# RBP_Dynamixel.net
KiCad netlist of a schematic drawn in EAGLE
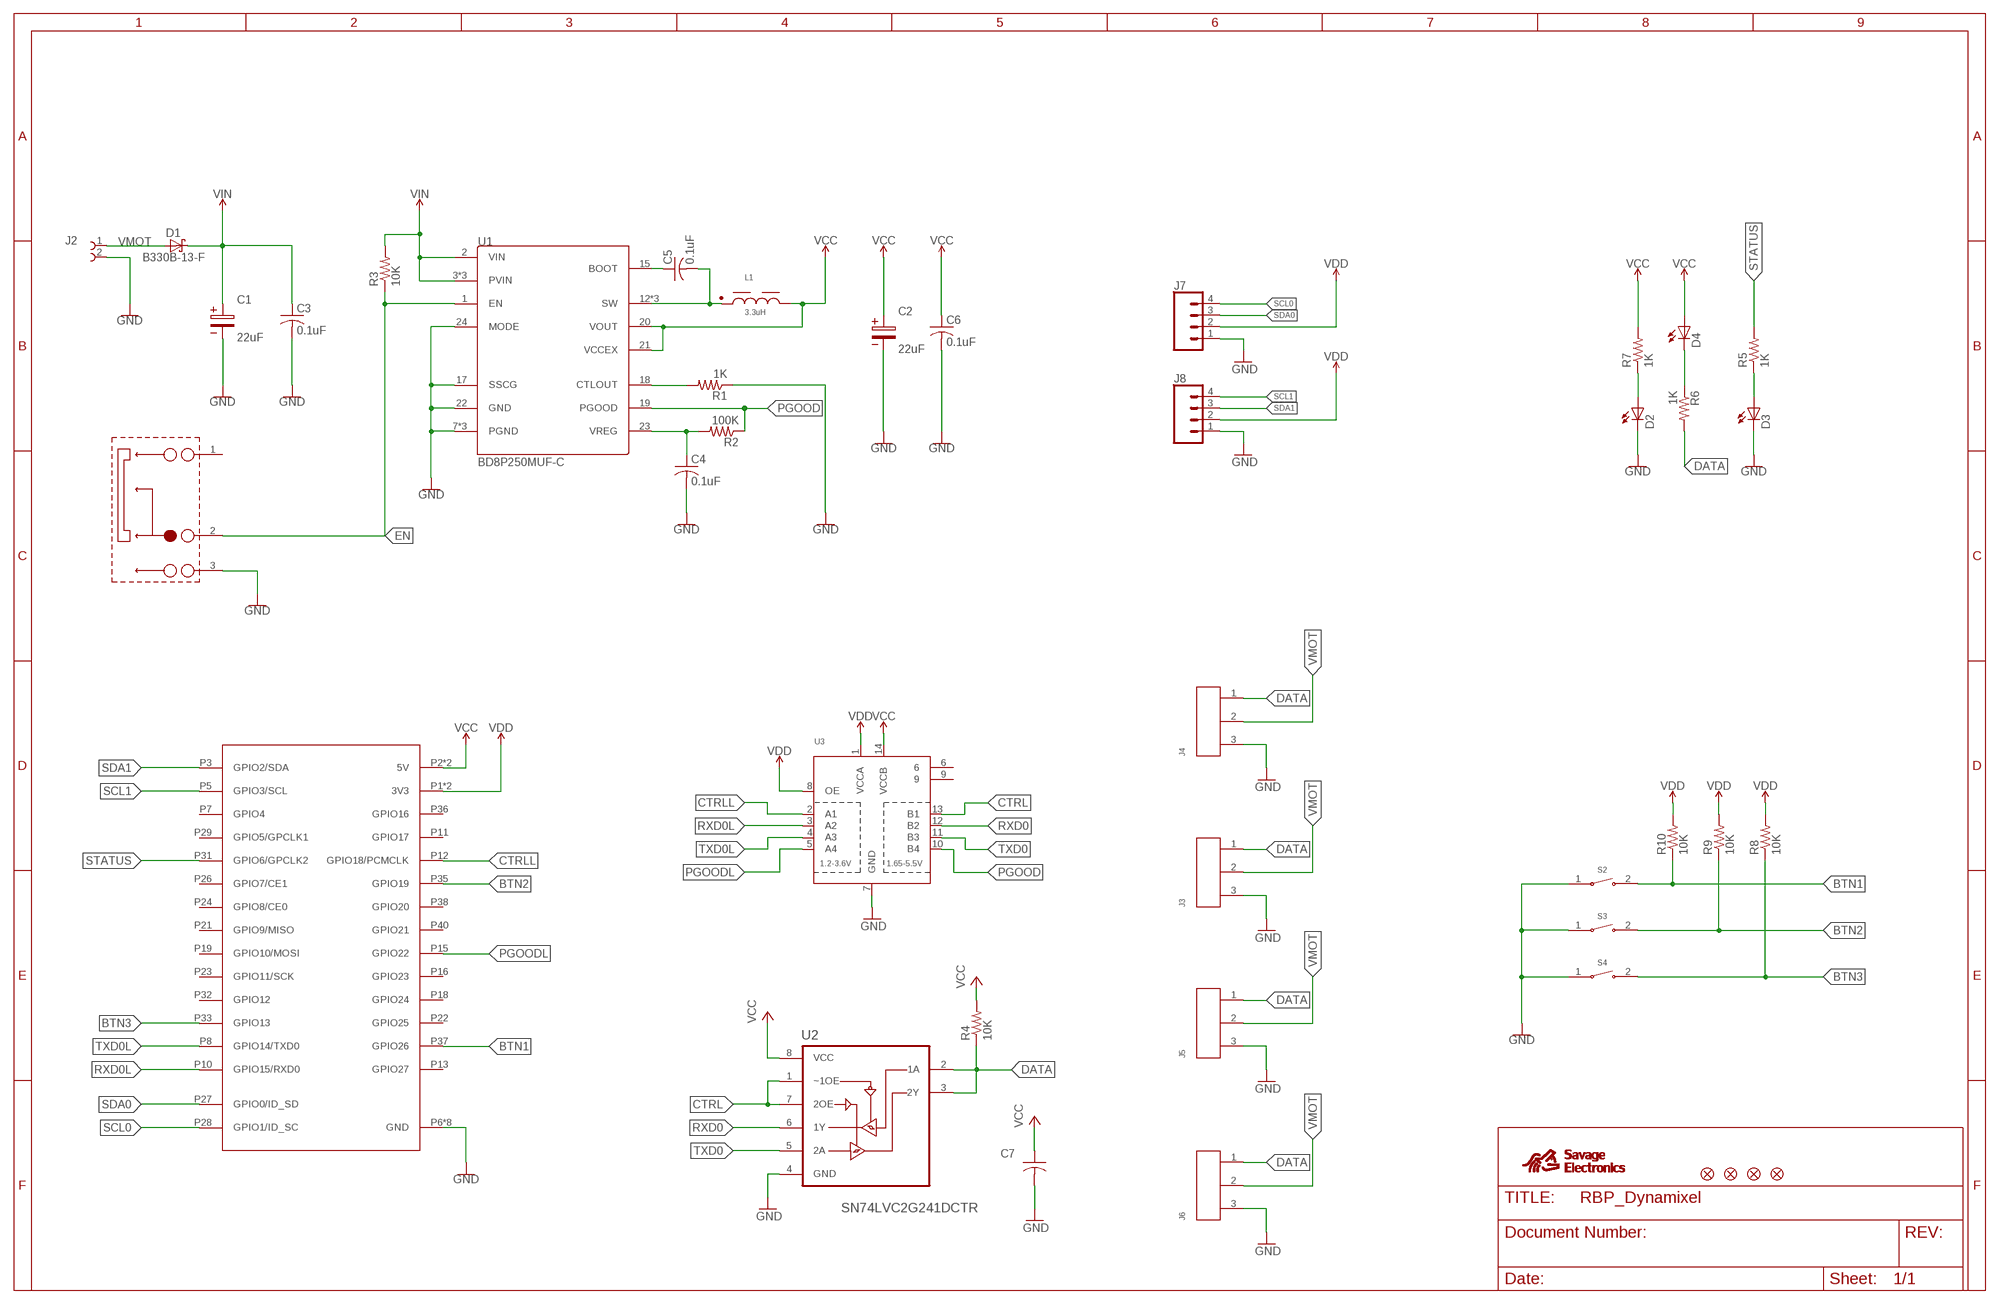
[diagram p0: schematic, sheet 1]

(export (version "E")
  (design (tool "Eeschema 10.0.6"))
  (components
    (comp (ref "C1")
      (value "22uF")
      (footprint "eagle-import:3.5X1.6X2.1(BXCXA)")
      (libsource (lib "eagle-import") (part "WCAP-ASLI_865080643007_6,3X5,5"))
    )
    (comp (ref "C2")
      (value "22uF")
      (footprint "eagle-import:3.5X1.6X2.1(BXCXA)")
      (libsource (lib "eagle-import") (part "WCAP-ASLI_865080643008_6,3X5,5"))
    )
    (comp (ref "C3")
      (value "0.1uF")
      (footprint "eagle-import:C0805")
      (libsource (lib "eagle-import") (part "C-USC0805"))
    )
    (comp (ref "C4")
      (value "0.1uF")
      (footprint "eagle-import:C0805")
      (libsource (lib "eagle-import") (part "C-USC0805"))
    )
    (comp (ref "C5")
      (value "0.1uF")
      (footprint "eagle-import:C0603")
      (libsource (lib "eagle-import") (part "C-USC0603"))
    )
    (comp (ref "C6")
      (value "0.1uF")
      (footprint "eagle-import:C0805")
      (libsource (lib "eagle-import") (part "C-USC0805"))
    )
    (comp (ref "C7")
      (value "1uF")
      (footprint "eagle-import:C0603")
      (libsource (lib "eagle-import") (part "C-USC0603"))
    )
    (comp (ref "D1")
      (value "B330B-13-F")
      (footprint "eagle-import:DIONM4336X250N")
      (libsource (lib "eagle-import") (part "B330B-13-F"))
    )
    (comp (ref "D2")
      (value "LEDCHIP-LED0805")
      (footprint "eagle-import:CHIP-LED0805")
      (libsource (lib "eagle-import") (part "LEDCHIP-LED0805"))
    )
    (comp (ref "D3")
      (value "LEDCHIP-LED0805")
      (footprint "eagle-import:CHIP-LED0805")
      (libsource (lib "eagle-import") (part "LEDCHIP-LED0805"))
    )
    (comp (ref "D4")
      (value "LEDCHIP-LED0805")
      (footprint "eagle-import:CHIP-LED0805")
      (libsource (lib "eagle-import") (part "LEDCHIP-LED0805"))
    )
    (comp (ref "FID1")
      (value "FIDUCIAL\"\"")
      (footprint "eagle-import:FIDUCIAL_1MM")
      (libsource (lib "eagle-import") (part "FIDUCIAL{dblquote}{dblquote}"))
    )
    (comp (ref "FID2")
      (value "FIDUCIAL\"\"")
      (footprint "eagle-import:FIDUCIAL_1MM")
      (libsource (lib "eagle-import") (part "FIDUCIAL{dblquote}{dblquote}"))
    )
    (comp (ref "FID3")
      (value "FIDUCIAL\"\"")
      (footprint "eagle-import:FIDUCIAL_1MM")
      (libsource (lib "eagle-import") (part "FIDUCIAL{dblquote}{dblquote}"))
    )
    (comp (ref "FID4")
      (value "FIDUCIAL\"\"")
      (footprint "eagle-import:FIDUCIAL_1MM")
      (libsource (lib "eagle-import") (part "FIDUCIAL{dblquote}{dblquote}"))
    )
    (comp (ref "J1")
      (value "RBPZERO")
      (footprint "eagle-import:61004021821_RASPBERRYPIZERO")
      (libsource (lib "eagle-import") (part "RBPZERO"))
    )
    (comp (ref "J2")
      (value "691137910002")
      (footprint "eagle-import:691137910002")
      (libsource (lib "eagle-import") (part "691137910002"))
    )
    (comp (ref "J3")
      (value "64600311622")
      (footprint "eagle-import:64600311622")
      (libsource (lib "eagle-import") (part "64600311622"))
    )
    (comp (ref "J4")
      (value "64600311622")
      (footprint "eagle-import:64600311622")
      (libsource (lib "eagle-import") (part "64600311622"))
    )
    (comp (ref "J5")
      (value "64600311622")
      (footprint "eagle-import:64600311622")
      (libsource (lib "eagle-import") (part "64600311622"))
    )
    (comp (ref "J6")
      (value "64600311622")
      (footprint "eagle-import:64600311622")
      (libsource (lib "eagle-import") (part "64600311622"))
    )
    (comp (ref "J7")
      (value "CONN_04SMD2")
      (footprint "eagle-import:1X04_1MM_RA")
      (libsource (lib "eagle-import") (part "CONN_04SMD2"))
    )
    (comp (ref "J8")
      (value "CONN_04SMD2")
      (footprint "eagle-import:1X04_1MM_RA")
      (libsource (lib "eagle-import") (part "CONN_04SMD2"))
    )
    (comp (ref "L1")
      (value "3.3uH")
      (footprint "eagle-import:WE-LQFS_48X8")
      (libsource (lib "eagle-import") (part "WE-LQFS_4818_74406042022"))
    )
    (comp (ref "R1")
      (value "1K")
      (footprint "eagle-import:R0805")
      (libsource (lib "eagle-import") (part "R-US_R0805"))
    )
    (comp (ref "R2")
      (value "100K")
      (footprint "eagle-import:R0805")
      (libsource (lib "eagle-import") (part "R-US_R0805"))
    )
    (comp (ref "R3")
      (value "10K")
      (footprint "eagle-import:R0805")
      (libsource (lib "eagle-import") (part "R-US_R0805"))
    )
    (comp (ref "R4")
      (value "10K")
      (footprint "eagle-import:R0805")
      (libsource (lib "eagle-import") (part "R-US_R0805"))
    )
    (comp (ref "R5")
      (value "1K")
      (footprint "eagle-import:R0805")
      (libsource (lib "eagle-import") (part "R-US_R0805"))
    )
    (comp (ref "R6")
      (value "1K")
      (footprint "eagle-import:R0805")
      (libsource (lib "eagle-import") (part "R-US_R0805"))
    )
    (comp (ref "R7")
      (value "1K")
      (footprint "eagle-import:R0805")
      (libsource (lib "eagle-import") (part "R-US_R0805"))
    )
    (comp (ref "R8")
      (value "10K")
      (footprint "eagle-import:R0805")
      (libsource (lib "eagle-import") (part "R-US_R0805"))
    )
    (comp (ref "R9")
      (value "10K")
      (footprint "eagle-import:R0805")
      (libsource (lib "eagle-import") (part "R-US_R0805"))
    )
    (comp (ref "R10")
      (value "10K")
      (footprint "eagle-import:R0805")
      (libsource (lib "eagle-import") (part "R-US_R0805"))
    )
    (comp (ref "S1")
      (value "450404015514")
      (footprint "eagle-import:450404015514")
      (libsource (lib "eagle-import") (part "450404015514"))
    )
    (comp (ref "S2")
      (value "434123025826-2PIN")
      (footprint "eagle-import:434123025826-2PIN")
      (libsource (lib "eagle-import") (part "434123025826-2PIN"))
    )
    (comp (ref "S3")
      (value "434123025826-2PIN")
      (footprint "eagle-import:434123025826-2PIN")
      (libsource (lib "eagle-import") (part "434123025826-2PIN"))
    )
    (comp (ref "S4")
      (value "434123025826-2PIN")
      (footprint "eagle-import:434123025826-2PIN")
      (libsource (lib "eagle-import") (part "434123025826-2PIN"))
    )
    (comp (ref "U1")
      (value "BD8P250MUF-C")
      (footprint "eagle-import:QFN50P400X400X100-25N")
      (libsource (lib "eagle-import") (part "BD8P250MUF-C"))
    )
    (comp (ref "U2")
      (value "SN74LVC2G241DCTR")
      (footprint "eagle-import:SOP65P400X130-8N")
      (fields (field (name "MF") "Texas Instruments") (field (name "MP") "SN74LVC2G241"))
      (libsource (lib "eagle-import") (part "SN74LVC2G241"))
    )
    (comp (ref "U3")
      (value "TXB0104PWR")
      (footprint "eagle-import:TSSOP14")
      (libsource (lib "eagle-import") (part "TXB0104PWR"))
    )
  )
  (nets
    (net (code "1") (name "BTN1") (class "Default")
      (node (ref "J1") (pin "P37") (pinfunction "GPIO26_P37") (pintype "bidirectional"))
      (node (ref "R10") (pin "1") (pinfunction "1_1") (pintype "passive"))
      (node (ref "S2") (pin "2") (pinfunction "2_2") (pintype "passive"))
    )
    (net (code "2") (name "BTN2") (class "Default")
      (node (ref "J1") (pin "P35") (pinfunction "GPIO19_P35") (pintype "bidirectional"))
      (node (ref "R9") (pin "1") (pinfunction "1_1") (pintype "passive"))
      (node (ref "S3") (pin "2") (pinfunction "2_2") (pintype "passive"))
    )
    (net (code "3") (name "BTN3") (class "Default")
      (node (ref "J1") (pin "P33") (pinfunction "GPIO13_P33") (pintype "bidirectional"))
      (node (ref "R8") (pin "1") (pinfunction "1_1") (pintype "passive"))
      (node (ref "S4") (pin "2") (pinfunction "2_2") (pintype "passive"))
    )
    (net (code "4") (name "CTRL") (class "Default")
      (node (ref "U2") (pin "1") (pinfunction "~{1OE}_1") (pintype "input"))
      (node (ref "U2") (pin "7") (pinfunction "2OE_7") (pintype "input"))
      (node (ref "U3") (pin "13") (pinfunction "B1_13") (pintype "bidirectional"))
    )
    (net (code "5") (name "CTRLL") (class "Default")
      (node (ref "J1") (pin "P12") (pinfunction "GPIO18/PCMCLK_P12") (pintype "bidirectional"))
      (node (ref "U3") (pin "2") (pinfunction "A1_2") (pintype "bidirectional"))
    )
    (net (code "6") (name "DATA") (class "Default")
      (node (ref "J3") (pin "1") (pinfunction "1_1") (pintype "passive"))
      (node (ref "J4") (pin "1") (pinfunction "1_1") (pintype "passive"))
      (node (ref "J5") (pin "1") (pinfunction "1_1") (pintype "passive"))
      (node (ref "J6") (pin "1") (pinfunction "1_1") (pintype "passive"))
      (node (ref "R4") (pin "1") (pinfunction "1_1") (pintype "passive"))
      (node (ref "R6") (pin "2") (pinfunction "2_2") (pintype "passive"))
      (node (ref "U2") (pin "2") (pinfunction "1A_2") (pintype "input"))
      (node (ref "U2") (pin "3") (pinfunction "2Y_3") (pintype "output"))
    )
    (net (code "7") (name "EN") (class "Default")
      (node (ref "R3") (pin "1") (pinfunction "1_1") (pintype "passive"))
      (node (ref "S1") (pin "2") (pinfunction "2_2") (pintype "passive"))
      (node (ref "U1") (pin "1") (pinfunction "EN_1") (pintype "bidirectional"))
    )
    (net (code "8") (name "GND") (class "Default")
      (node (ref "C1") (pin "2") (pinfunction "2_2") (pintype "passive"))
      (node (ref "C2") (pin "2") (pinfunction "2_2") (pintype "passive"))
      (node (ref "C3") (pin "2") (pinfunction "2_2") (pintype "passive"))
      (node (ref "C4") (pin "2") (pinfunction "2_2") (pintype "passive"))
      (node (ref "C6") (pin "2") (pinfunction "2_2") (pintype "passive"))
      (node (ref "C7") (pin "2") (pinfunction "2_2") (pintype "passive"))
      (node (ref "D2") (pin "C") (pinfunction "C_C") (pintype "passive"))
      (node (ref "D3") (pin "C") (pinfunction "C_C") (pintype "passive"))
      (node (ref "J1") (pin "P14") (pinfunction "GND_P14") (pintype "bidirectional"))
      (node (ref "J1") (pin "P20") (pinfunction "GND_P20") (pintype "bidirectional"))
      (node (ref "J1") (pin "P25") (pinfunction "GND_P25") (pintype "bidirectional"))
      (node (ref "J1") (pin "P30") (pinfunction "GND_P30") (pintype "bidirectional"))
      (node (ref "J1") (pin "P34") (pinfunction "GND_P34") (pintype "bidirectional"))
      (node (ref "J1") (pin "P39") (pinfunction "GND_P39") (pintype "bidirectional"))
      (node (ref "J1") (pin "P6") (pinfunction "GND_P6") (pintype "bidirectional"))
      (node (ref "J1") (pin "P9") (pinfunction "GND_P9") (pintype "bidirectional"))
      (node (ref "J2") (pin "2") (pinfunction "2_2") (pintype "passive"))
      (node (ref "J3") (pin "3") (pinfunction "3_3") (pintype "passive"))
      (node (ref "J4") (pin "3") (pinfunction "3_3") (pintype "passive"))
      (node (ref "J5") (pin "3") (pinfunction "3_3") (pintype "passive"))
      (node (ref "J6") (pin "3") (pinfunction "3_3") (pintype "passive"))
      (node (ref "J7") (pin "1") (pinfunction "1_1") (pintype "passive"))
      (node (ref "J8") (pin "1") (pinfunction "1_1") (pintype "passive"))
      (node (ref "R1") (pin "1") (pinfunction "1_1") (pintype "passive"))
      (node (ref "S1") (pin "3") (pinfunction "3_3") (pintype "passive"))
      (node (ref "S2") (pin "1") (pinfunction "1_1") (pintype "passive"))
      (node (ref "S3") (pin "1") (pinfunction "1_1") (pintype "passive"))
      (node (ref "S4") (pin "1") (pinfunction "1_1") (pintype "passive"))
      (node (ref "U1") (pin "17") (pinfunction "SSCG_17") (pintype "bidirectional"))
      (node (ref "U1") (pin "22") (pinfunction "GND_22") (pintype "bidirectional"))
      (node (ref "U1") (pin "24") (pinfunction "MODE_24") (pintype "bidirectional"))
      (node (ref "U1") (pin "25") (pinfunction "PGND_25") (pintype "bidirectional"))
      (node (ref "U1") (pin "7") (pinfunction "PGND_7") (pintype "bidirectional"))
      (node (ref "U1") (pin "8") (pinfunction "PGND_8") (pintype "bidirectional"))
      (node (ref "U2") (pin "4") (pinfunction "GND_4") (pintype "passive"))
      (node (ref "U3") (pin "7") (pinfunction "GND_7") (pintype "bidirectional"))
    )
    (net (code "9") (name "Net-(C5-Pad2)") (class "Default")
      (node (ref "C5") (pin "2") (pinfunction "2_2") (pintype "passive"))
      (node (ref "L1") (pin "1") (pinfunction "1_1") (pintype "passive"))
      (node (ref "U1") (pin "12") (pinfunction "SW_12") (pintype "bidirectional"))
      (node (ref "U1") (pin "13") (pinfunction "SW_13") (pintype "bidirectional"))
      (node (ref "U1") (pin "14") (pinfunction "SW_14") (pintype "bidirectional"))
    )
    (net (code "10") (name "Net-(D2-PadA)") (class "Default")
      (node (ref "D2") (pin "A") (pinfunction "A_A") (pintype "passive"))
      (node (ref "R7") (pin "1") (pinfunction "1_1") (pintype "passive"))
    )
    (net (code "11") (name "Net-(D3-PadA)") (class "Default")
      (node (ref "D3") (pin "A") (pinfunction "A_A") (pintype "passive"))
      (node (ref "R5") (pin "1") (pinfunction "1_1") (pintype "passive"))
    )
    (net (code "12") (name "Net-(D4-PadC)") (class "Default")
      (node (ref "D4") (pin "C") (pinfunction "C_C") (pintype "passive"))
      (node (ref "R6") (pin "1") (pinfunction "1_1") (pintype "passive"))
    )
    (net (code "13") (name "Net-(U1-BOOT)") (class "Default")
      (node (ref "C5") (pin "1") (pinfunction "1_1") (pintype "passive"))
      (node (ref "U1") (pin "15") (pinfunction "BOOT_15") (pintype "bidirectional"))
    )
    (net (code "14") (name "Net-(U1-CTLOUT)") (class "Default")
      (node (ref "R1") (pin "2") (pinfunction "2_2") (pintype "passive"))
      (node (ref "U1") (pin "18") (pinfunction "CTLOUT_18") (pintype "bidirectional"))
    )
    (net (code "15") (name "Net-(U1-VREG)") (class "Default")
      (node (ref "C4") (pin "1") (pinfunction "1_1") (pintype "passive"))
      (node (ref "R2") (pin "2") (pinfunction "2_2") (pintype "passive"))
      (node (ref "U1") (pin "23") (pinfunction "VREG_23") (pintype "bidirectional"))
    )
    (net (code "16") (name "PGOOD") (class "Default")
      (node (ref "R2") (pin "1") (pinfunction "1_1") (pintype "passive"))
      (node (ref "U1") (pin "19") (pinfunction "PGOOD_19") (pintype "bidirectional"))
      (node (ref "U3") (pin "10") (pinfunction "B4_10") (pintype "bidirectional"))
    )
    (net (code "17") (name "PGOODL") (class "Default")
      (node (ref "J1") (pin "P15") (pinfunction "GPIO22_P15") (pintype "bidirectional"))
      (node (ref "U3") (pin "5") (pinfunction "A4_5") (pintype "bidirectional"))
    )
    (net (code "18") (name "RXD0") (class "Default")
      (node (ref "U2") (pin "6") (pinfunction "1Y_6") (pintype "output"))
      (node (ref "U3") (pin "12") (pinfunction "B2_12") (pintype "bidirectional"))
    )
    (net (code "19") (name "RXD0L") (class "Default")
      (node (ref "J1") (pin "P10") (pinfunction "GPIO15/RXD0_P10") (pintype "bidirectional"))
      (node (ref "U3") (pin "3") (pinfunction "A2_3") (pintype "bidirectional"))
    )
    (net (code "20") (name "SCL0") (class "Default")
      (node (ref "J1") (pin "P28") (pinfunction "GPIO1/ID_SC_P28") (pintype "bidirectional"))
      (node (ref "J7") (pin "4") (pinfunction "4_4") (pintype "passive"))
    )
    (net (code "21") (name "SCL1") (class "Default")
      (node (ref "J1") (pin "P5") (pinfunction "GPIO3/SCL_P5") (pintype "bidirectional"))
      (node (ref "J8") (pin "4") (pinfunction "4_4") (pintype "passive"))
    )
    (net (code "22") (name "SDA0") (class "Default")
      (node (ref "J1") (pin "P27") (pinfunction "GPIO0/ID_SD_P27") (pintype "bidirectional"))
      (node (ref "J7") (pin "3") (pinfunction "3_3") (pintype "passive"))
    )
    (net (code "23") (name "SDA1") (class "Default")
      (node (ref "J1") (pin "P3") (pinfunction "GPIO2/SDA_P3") (pintype "bidirectional"))
      (node (ref "J8") (pin "3") (pinfunction "3_3") (pintype "passive"))
    )
    (net (code "24") (name "STATUS") (class "Default")
      (node (ref "J1") (pin "P31") (pinfunction "GPIO6/GPCLK2_P31") (pintype "bidirectional"))
      (node (ref "R5") (pin "2") (pinfunction "2_2") (pintype "passive"))
    )
    (net (code "25") (name "TXD0") (class "Default")
      (node (ref "U2") (pin "5") (pinfunction "2A_5") (pintype "input"))
      (node (ref "U3") (pin "11") (pinfunction "B3_11") (pintype "bidirectional"))
    )
    (net (code "26") (name "TXD0L") (class "Default")
      (node (ref "J1") (pin "P8") (pinfunction "GPIO14/TXD0_P8") (pintype "bidirectional"))
      (node (ref "U3") (pin "4") (pinfunction "A3_4") (pintype "bidirectional"))
    )
    (net (code "27") (name "VCC") (class "Default")
      (node (ref "C2") (pin "1") (pinfunction "1_1") (pintype "passive"))
      (node (ref "C6") (pin "1") (pinfunction "1_1") (pintype "passive"))
      (node (ref "C7") (pin "1") (pinfunction "1_1") (pintype "passive"))
      (node (ref "D4") (pin "A") (pinfunction "A_A") (pintype "passive"))
      (node (ref "J1") (pin "P2") (pinfunction "5V_P2") (pintype "bidirectional"))
      (node (ref "J1") (pin "P4") (pinfunction "5V_P4") (pintype "bidirectional"))
      (node (ref "L1") (pin "2") (pinfunction "2_2") (pintype "passive"))
      (node (ref "R4") (pin "2") (pinfunction "2_2") (pintype "passive"))
      (node (ref "R7") (pin "2") (pinfunction "2_2") (pintype "passive"))
      (node (ref "U1") (pin "20") (pinfunction "VOUT_20") (pintype "bidirectional"))
      (node (ref "U1") (pin "21") (pinfunction "VCCEX_21") (pintype "bidirectional"))
      (node (ref "U2") (pin "8") (pinfunction "VCC_8") (pintype "power_in"))
      (node (ref "U3") (pin "14") (pinfunction "VCCB_14") (pintype "bidirectional"))
    )
    (net (code "28") (name "VDD") (class "Default")
      (node (ref "J1") (pin "P1") (pinfunction "3V3_P1") (pintype "bidirectional"))
      (node (ref "J1") (pin "P17") (pinfunction "3V3_P17") (pintype "bidirectional"))
      (node (ref "J7") (pin "2") (pinfunction "2_2") (pintype "passive"))
      (node (ref "J8") (pin "2") (pinfunction "2_2") (pintype "passive"))
      (node (ref "R10") (pin "2") (pinfunction "2_2") (pintype "passive"))
      (node (ref "R8") (pin "2") (pinfunction "2_2") (pintype "passive"))
      (node (ref "R9") (pin "2") (pinfunction "2_2") (pintype "passive"))
      (node (ref "U3") (pin "1") (pinfunction "VCCA_1") (pintype "bidirectional"))
      (node (ref "U3") (pin "8") (pinfunction "OE_8") (pintype "bidirectional"))
    )
    (net (code "29") (name "VIN") (class "Default")
      (node (ref "C1") (pin "1") (pinfunction "1_1") (pintype "passive"))
      (node (ref "C3") (pin "1") (pinfunction "1_1") (pintype "passive"))
      (node (ref "D1") (pin "1") (pinfunction "C_1") (pintype "passive"))
      (node (ref "R3") (pin "2") (pinfunction "2_2") (pintype "passive"))
      (node (ref "U1") (pin "2") (pinfunction "VIN_2") (pintype "bidirectional"))
      (node (ref "U1") (pin "3") (pinfunction "PVIN_3") (pintype "bidirectional"))
      (node (ref "U1") (pin "4") (pinfunction "PVIN_4") (pintype "bidirectional"))
      (node (ref "U1") (pin "5") (pinfunction "PVIN_5") (pintype "bidirectional"))
    )
    (net (code "30") (name "VMOT") (class "Default")
      (node (ref "D1") (pin "2") (pinfunction "A_2") (pintype "passive"))
      (node (ref "J2") (pin "1") (pinfunction "1_1") (pintype "passive"))
      (node (ref "J3") (pin "2") (pinfunction "2_2") (pintype "passive"))
      (node (ref "J4") (pin "2") (pinfunction "2_2") (pintype "passive"))
      (node (ref "J5") (pin "2") (pinfunction "2_2") (pintype "passive"))
      (node (ref "J6") (pin "2") (pinfunction "2_2") (pintype "passive"))
    )
    (net (code "31") (name "unconnected-(J1-GPIO4-PadP7)") (class "Default")
      (node (ref "J1") (pin "P7") (pinfunction "GPIO4_P7") (pintype "bidirectional"))
    )
    (net (code "32") (name "unconnected-(J1-GPIO5{slash}GPCLK1-PadP29)") (class "Default")
      (node (ref "J1") (pin "P29") (pinfunction "GPIO5/GPCLK1_P29") (pintype "bidirectional"))
    )
    (net (code "33") (name "unconnected-(J1-GPIO7{slash}CE1-PadP26)") (class "Default")
      (node (ref "J1") (pin "P26") (pinfunction "GPIO7/CE1_P26") (pintype "bidirectional"))
    )
    (net (code "34") (name "unconnected-(J1-GPIO8{slash}CE0-PadP24)") (class "Default")
      (node (ref "J1") (pin "P24") (pinfunction "GPIO8/CE0_P24") (pintype "bidirectional"))
    )
    (net (code "35") (name "unconnected-(J1-GPIO9{slash}MISO-PadP21)") (class "Default")
      (node (ref "J1") (pin "P21") (pinfunction "GPIO9/MISO_P21") (pintype "bidirectional"))
    )
    (net (code "36") (name "unconnected-(J1-GPIO10{slash}MOSI-PadP19)") (class "Default")
      (node (ref "J1") (pin "P19") (pinfunction "GPIO10/MOSI_P19") (pintype "bidirectional"))
    )
    (net (code "37") (name "unconnected-(J1-GPIO11{slash}SCK-PadP23)") (class "Default")
      (node (ref "J1") (pin "P23") (pinfunction "GPIO11/SCK_P23") (pintype "bidirectional"))
    )
    (net (code "38") (name "unconnected-(J1-GPIO12-PadP32)") (class "Default")
      (node (ref "J1") (pin "P32") (pinfunction "GPIO12_P32") (pintype "bidirectional"))
    )
    (net (code "39") (name "unconnected-(J1-GPIO16-PadP36)") (class "Default")
      (node (ref "J1") (pin "P36") (pinfunction "GPIO16_P36") (pintype "bidirectional"))
    )
    (net (code "40") (name "unconnected-(J1-GPIO17-PadP11)") (class "Default")
      (node (ref "J1") (pin "P11") (pinfunction "GPIO17_P11") (pintype "bidirectional"))
    )
    (net (code "41") (name "unconnected-(J1-GPIO20-PadP38)") (class "Default")
      (node (ref "J1") (pin "P38") (pinfunction "GPIO20_P38") (pintype "bidirectional"))
    )
    (net (code "42") (name "unconnected-(J1-GPIO21-PadP40)") (class "Default")
      (node (ref "J1") (pin "P40") (pinfunction "GPIO21_P40") (pintype "bidirectional"))
    )
    (net (code "43") (name "unconnected-(J1-GPIO23-PadP16)") (class "Default")
      (node (ref "J1") (pin "P16") (pinfunction "GPIO23_P16") (pintype "bidirectional"))
    )
    (net (code "44") (name "unconnected-(J1-GPIO24-PadP18)") (class "Default")
      (node (ref "J1") (pin "P18") (pinfunction "GPIO24_P18") (pintype "bidirectional"))
    )
    (net (code "45") (name "unconnected-(J1-GPIO25-PadP22)") (class "Default")
      (node (ref "J1") (pin "P22") (pinfunction "GPIO25_P22") (pintype "bidirectional"))
    )
    (net (code "46") (name "unconnected-(J1-GPIO27-PadP13)") (class "Default")
      (node (ref "J1") (pin "P13") (pinfunction "GPIO27_P13") (pintype "bidirectional"))
    )
    (net (code "47") (name "unconnected-(S1-Pad1)") (class "Default")
      (node (ref "S1") (pin "1") (pinfunction "1_1") (pintype "passive"))
    )
    (net (code "48") (name "unconnected-(U3-Pad6)") (class "Default")
      (node (ref "U3") (pin "6") (pinfunction "6_6") (pintype "bidirectional"))
    )
    (net (code "49") (name "unconnected-(U3-Pad9)") (class "Default")
      (node (ref "U3") (pin "9") (pinfunction "9_9") (pintype "bidirectional"))
    )
  )
)
